# TS3USB221A_PINOUT.net
KiCad netlist of a schematic drawn in Altium Designer
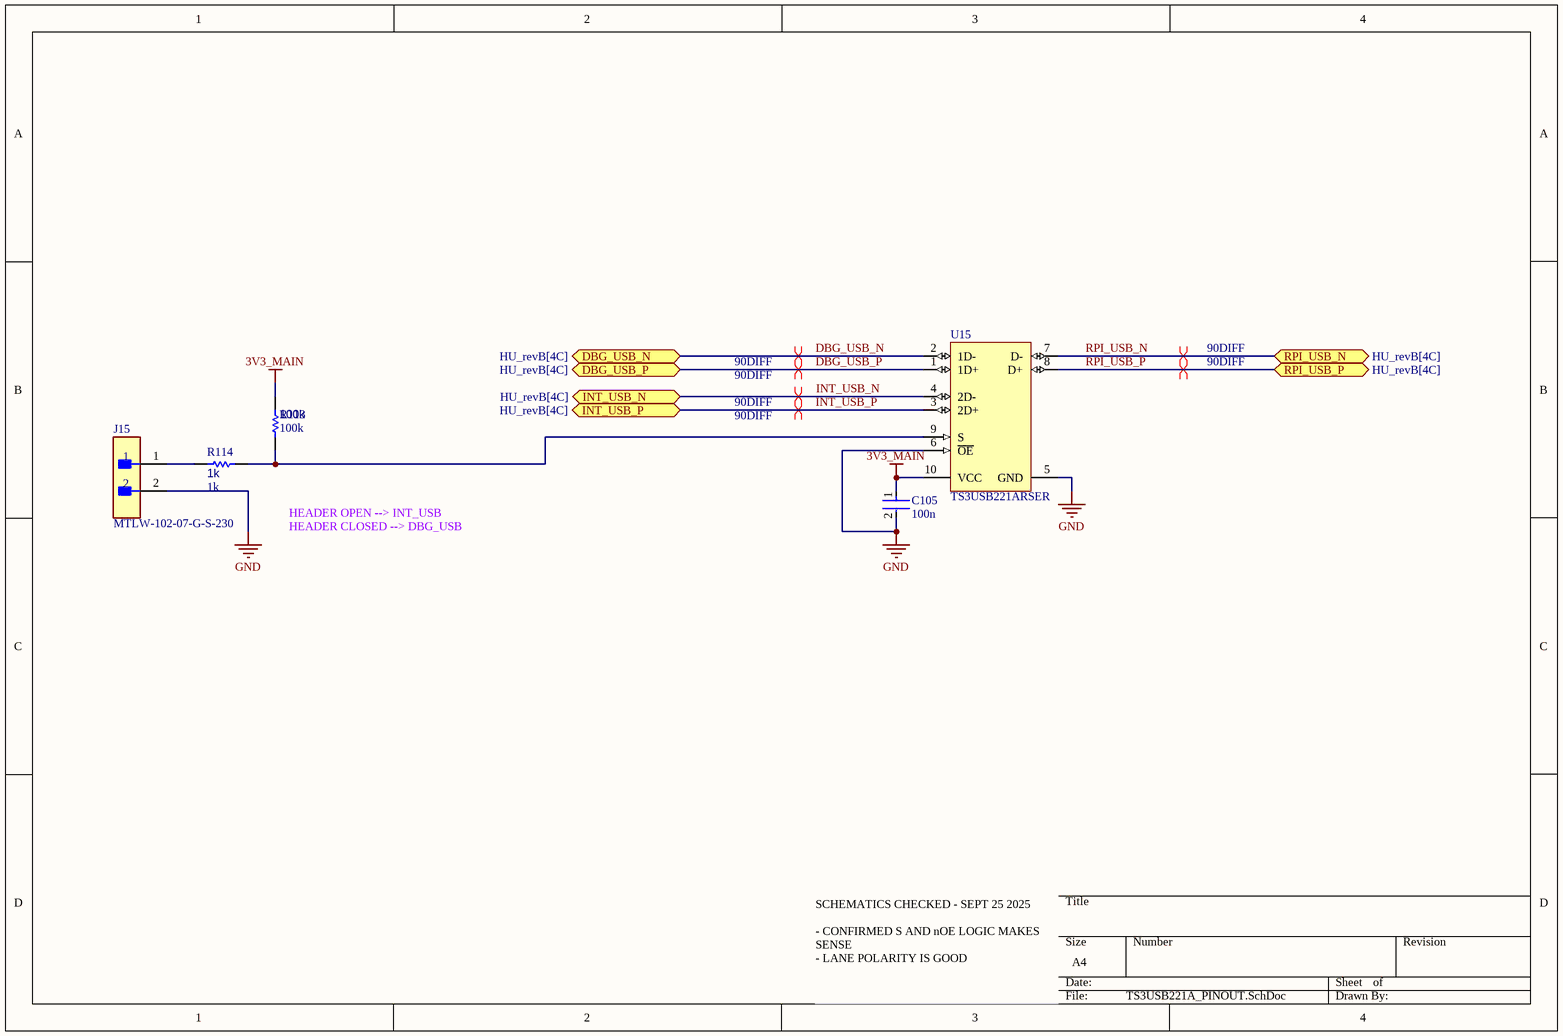
[diagram p0: TS3USB221A_PINOUT.SchDoc]

(export (version "E")
  (design (tool "Eeschema 10.0.6"))
  (components
    (comp (ref "C105")
      (value "100n")
      (footprint "FP-0402-L_1_0_0_05-W_0_5-IPC_A")
      (description "LARGE PADS, 0402 CAP, CHANGE COMMENT TO MATCH REAL P/N")
      (libsource (lib "Space Concordia") (part "b4654b650e69147ec39a6b967a45e02"))
    )
    (comp (ref "J15")
      (value "MTLW-102-07-G-S-230")
      (footprint "FP-MTLW-102-07-G-S-230-MFG")
      (description "CONN HEADER VERT 2POS 2.54MM")
      (libsource (lib "Altium Content Vault") (part "3bc925449376181038e59eaffc5286c"))
    )
    (comp (ref "R113")
      (value "100k")
      (footprint "R0603B")
      (description "Resistor")
      (fields (field (name "ALTIUM_VALUE") "100k"))
      (libsource (lib "Space Concordia") (part "Resistor"))
    )
    (comp (ref "R114")
      (value "1k")
      (footprint "R0603B")
      (description "Resistor")
      (fields (field (name "ALTIUM_VALUE") "1k"))
      (libsource (lib "Space Concordia") (part "Resistor"))
    )
    (comp (ref "U15")
      (value "TS3USB221ARSER")
      (footprint "RSE0010A_V")
      (fields (field (name "MANUFACTURER") "Texas Instruments"))
      (libsource (lib "Altium Content Vault") (part "TI-TS3USB221A-UQFN_RSE-10"))
    )
  )
  (nets
    (net (code "1") (name "/DBG_USB_N") (class "Default")
      (node (ref "U15") (pin "2") (pinfunction "1D-_2") (pintype "bidirectional"))
    )
    (net (code "2") (name "/DBG_USB_P") (class "Default")
      (node (ref "U15") (pin "1") (pinfunction "1D+_1") (pintype "bidirectional"))
    )
    (net (code "3") (name "/INT_USB_N") (class "Default")
      (node (ref "U15") (pin "4") (pinfunction "2D-_4") (pintype "bidirectional"))
    )
    (net (code "4") (name "/INT_USB_P") (class "Default")
      (node (ref "U15") (pin "3") (pinfunction "2D+_3") (pintype "bidirectional"))
    )
    (net (code "5") (name "/RPI_USB_N") (class "Default")
      (node (ref "U15") (pin "7") (pinfunction "D-_7") (pintype "bidirectional"))
    )
    (net (code "6") (name "/RPI_USB_P") (class "Default")
      (node (ref "U15") (pin "8") (pinfunction "D+_8") (pintype "bidirectional"))
    )
    (net (code "7") (name "3V3_MAIN") (class "Default")
      (node (ref "C105") (pin "1") (pinfunction "1_1") (pintype "passive"))
      (node (ref "R113") (pin "2") (pinfunction "2_2") (pintype "passive"))
      (node (ref "U15") (pin "10") (pinfunction "VCC_10") (pintype "power_in"))
    )
    (net (code "8") (name "GND") (class "Default")
      (node (ref "C105") (pin "2") (pinfunction "2_2") (pintype "passive"))
      (node (ref "J15") (pin "2") (pinfunction "2_2") (pintype "passive"))
      (node (ref "U15") (pin "5") (pinfunction "GND_5") (pintype "power_in"))
      (node (ref "U15") (pin "6") (pinfunction "~{OE}_6") (pintype "input"))
    )
    (net (code "9") (name "Net-(J15-Pad1)") (class "Default")
      (node (ref "J15") (pin "1") (pinfunction "1_1") (pintype "passive"))
      (node (ref "R114") (pin "2") (pinfunction "2_2") (pintype "passive"))
    )
    (net (code "10") (name "Net-(U15-S)") (class "Default")
      (node (ref "R113") (pin "1") (pinfunction "1_1") (pintype "passive"))
      (node (ref "R114") (pin "1") (pinfunction "1_1") (pintype "passive"))
      (node (ref "U15") (pin "9") (pinfunction "S_9") (pintype "input"))
    )
  )
)
